# MODE-SELECTOR.net
KiCad netlist of a schematic drawn in Altium Designer
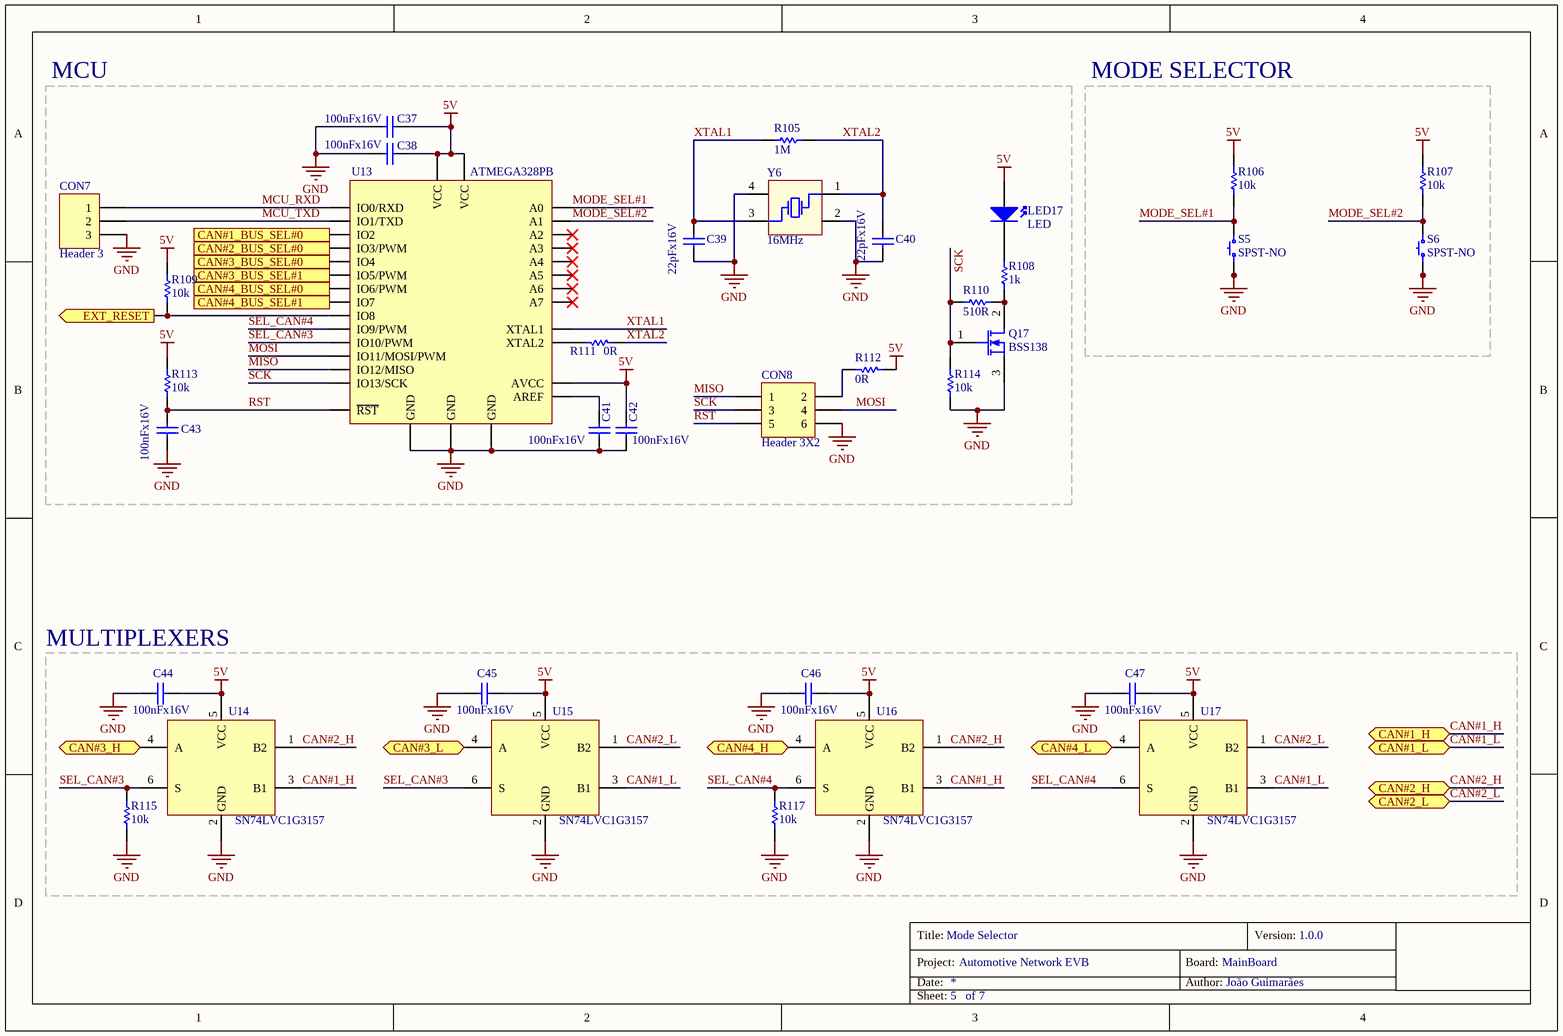
[diagram p0: MODE-SELECTOR.SchDoc]

(export (version "E")
  (design (tool "Eeschema 10.0.6"))
  (components
    (comp (ref "C37")
      (value "100nFx16V")
      (footprint "DISC-0603")
      (description "Capacitor")
      (libsource (lib "IntLib") (part "Cap"))
    )
    (comp (ref "C38")
      (value "100nFx16V")
      (footprint "DISC-0603")
      (description "Capacitor")
      (libsource (lib "IntLib") (part "Cap"))
    )
    (comp (ref "C39")
      (value "22pFx16V")
      (footprint "DISC-0603")
      (description "Capacitor")
      (libsource (lib "IntLib") (part "Cap"))
    )
    (comp (ref "C40")
      (value "22pFx16V")
      (footprint "DISC-0603")
      (description "Capacitor")
      (libsource (lib "IntLib") (part "Cap"))
    )
    (comp (ref "C41")
      (value "100nFx16V")
      (footprint "DISC-0603")
      (description "Capacitor")
      (libsource (lib "IntLib") (part "Cap"))
    )
    (comp (ref "C42")
      (value "100nFx16V")
      (footprint "DISC-0603")
      (description "Capacitor")
      (libsource (lib "IntLib") (part "Cap"))
    )
    (comp (ref "C43")
      (value "100nFx16V")
      (footprint "DISC-0603")
      (description "Capacitor")
      (libsource (lib "IntLib") (part "Cap"))
    )
    (comp (ref "C44")
      (value "100nFx16V")
      (footprint "DISC-0603")
      (description "Capacitor")
      (libsource (lib "IntLib") (part "Cap"))
    )
    (comp (ref "C45")
      (value "100nFx16V")
      (footprint "DISC-0603")
      (description "Capacitor")
      (libsource (lib "IntLib") (part "Cap"))
    )
    (comp (ref "C46")
      (value "100nFx16V")
      (footprint "DISC-0603")
      (description "Capacitor")
      (libsource (lib "IntLib") (part "Cap"))
    )
    (comp (ref "C47")
      (value "100nFx16V")
      (footprint "DISC-0603")
      (description "Capacitor")
      (libsource (lib "IntLib") (part "Cap"))
    )
    (comp (ref "CON7")
      (value "Header 3")
      (footprint "CON-HEADER-1X3-PTH")
      (description "Header, 3-Pin")
      (libsource (lib "IntLib") (part "Header 3"))
    )
    (comp (ref "CON8")
      (value "Header 3X2")
      (footprint "CON-HEADER-2X3-SMD")
      (description "Header, 3-Pin, Dual row")
      (libsource (lib "IntLib") (part "Header 3X2"))
    )
    (comp (ref "LED17") (value "LED") (footprint "DISC-LED-1206") (libsource (lib "IntLib") (part "LED")))
    (comp (ref "Q17")
      (value "BSS138")
      (footprint "DISC-SOT-23")
      (description "Transistor NMOS")
      (libsource (lib "IntLib") (part "Transistor-NMOS(GDS)"))
    )
    (comp (ref "R105")
      (value "1M")
      (footprint "DISC-0603")
      (description "Resistor")
      (libsource (lib "IntLib") (part "Res"))
    )
    (comp (ref "R106")
      (value "10k")
      (footprint "DISC-0603")
      (description "Resistor")
      (libsource (lib "IntLib") (part "Res"))
    )
    (comp (ref "R107")
      (value "10k")
      (footprint "DISC-0603")
      (description "Resistor")
      (libsource (lib "IntLib") (part "Res"))
    )
    (comp (ref "R108") (value "1k") (footprint "DISC-0603") (libsource (lib "IntLib") (part "Res")))
    (comp (ref "R109")
      (value "10k")
      (footprint "DISC-0603")
      (description "Resistor")
      (libsource (lib "IntLib") (part "Res"))
    )
    (comp (ref "R110") (value "510R") (footprint "DISC-0603") (libsource (lib "IntLib") (part "Res")))
    (comp (ref "R111")
      (value "0R")
      (footprint "DISC-0603")
      (description "Resistor")
      (libsource (lib "IntLib") (part "Res"))
    )
    (comp (ref "R112")
      (value "0R")
      (footprint "DISC-0603")
      (description "Resistor")
      (libsource (lib "IntLib") (part "Res"))
    )
    (comp (ref "R113")
      (value "10k")
      (footprint "DISC-0603")
      (description "Resistor")
      (libsource (lib "IntLib") (part "Res"))
    )
    (comp (ref "R114") (value "10k") (footprint "DISC-0603") (libsource (lib "IntLib") (part "Res")))
    (comp (ref "R115")
      (value "10k")
      (footprint "DISC-0603")
      (description "Resistor")
      (libsource (lib "IntLib") (part "Res"))
    )
    (comp (ref "R117")
      (value "10k")
      (footprint "DISC-0603")
      (description "Resistor")
      (libsource (lib "IntLib") (part "Res"))
    )
    (comp (ref "S5")
      (value "SPST-NO")
      (footprint "DISC-PUSHBUTTON-4P-PTH")
      (libsource (lib "IntLib") (part "SPST-NO"))
    )
    (comp (ref "S6")
      (value "SPST-NO")
      (footprint "DISC-PUSHBUTTON-4P-PTH")
      (libsource (lib "IntLib") (part "SPST-NO"))
    )
    (comp (ref "U13")
      (value "ATMEGA328PB")
      (footprint "CI-QFP-32")
      (description "8-bit AVR® RISC-based microcontroller (MCU) with picoPower® technology.")
      (libsource (lib "IntLib") (part "ATMEGA328PB-AU"))
    )
    (comp (ref "U14")
      (value "SN74LVC1G3157")
      (footprint "CI-SOT-23-6")
      (description "Single-Pole Double-Throw Analog Switch")
      (libsource (lib "IntLib") (part "SN74LVC1G3157DBVR"))
    )
    (comp (ref "U15")
      (value "SN74LVC1G3157")
      (footprint "CI-SOT-23-6")
      (description "Single-Pole Double-Throw Analog Switch")
      (libsource (lib "IntLib") (part "SN74LVC1G3157DBVR"))
    )
    (comp (ref "U16")
      (value "SN74LVC1G3157")
      (footprint "CI-SOT-23-6")
      (description "Single-Pole Double-Throw Analog Switch")
      (libsource (lib "IntLib") (part "SN74LVC1G3157DBVR"))
    )
    (comp (ref "U17")
      (value "SN74LVC1G3157")
      (footprint "CI-SOT-23-6")
      (description "Single-Pole Double-Throw Analog Switch")
      (libsource (lib "IntLib") (part "SN74LVC1G3157DBVR"))
    )
    (comp (ref "Y6")
      (value "16MHz")
      (footprint "DISC-CRYSTAL-4P-3.2X2.5")
      (description "XTAL-4-PIN")
      (libsource (lib "IntLib") (part "XTAL-4-PIN"))
    )
  )
  (nets
    (net (code "1") (name "/CAN#1_BUS_SEL#0") (class "Default")
      (node (ref "U13") (pin "32") (pinfunction "IO2_32") (pintype "passive"))
    )
    (net (code "2") (name "/CAN#1_H") (class "Default")
      (node (ref "U14") (pin "3") (pinfunction "B1_3") (pintype "passive"))
      (node (ref "U16") (pin "3") (pinfunction "B1_3") (pintype "passive"))
    )
    (net (code "3") (name "/CAN#1_L") (class "Default")
      (node (ref "U15") (pin "3") (pinfunction "B1_3") (pintype "passive"))
      (node (ref "U17") (pin "3") (pinfunction "B1_3") (pintype "passive"))
    )
    (net (code "4") (name "/CAN#2_BUS_SEL#0") (class "Default")
      (node (ref "U13") (pin "1") (pinfunction "IO3/PWM_1") (pintype "passive"))
    )
    (net (code "5") (name "/CAN#2_H") (class "Default")
      (node (ref "U14") (pin "1") (pinfunction "B2_1") (pintype "passive"))
      (node (ref "U16") (pin "1") (pinfunction "B2_1") (pintype "passive"))
    )
    (net (code "6") (name "/CAN#2_L") (class "Default")
      (node (ref "U15") (pin "1") (pinfunction "B2_1") (pintype "passive"))
      (node (ref "U17") (pin "1") (pinfunction "B2_1") (pintype "passive"))
    )
    (net (code "7") (name "/CAN#3_BUS_SEL#0") (class "Default")
      (node (ref "U13") (pin "2") (pinfunction "IO4_2") (pintype "passive"))
    )
    (net (code "8") (name "/CAN#3_BUS_SEL#1") (class "Default")
      (node (ref "U13") (pin "9") (pinfunction "IO5/PWM_9") (pintype "passive"))
    )
    (net (code "9") (name "/CAN#3_H") (class "Default")
      (node (ref "U14") (pin "4") (pinfunction "A_4") (pintype "passive"))
    )
    (net (code "10") (name "/CAN#3_L") (class "Default")
      (node (ref "U15") (pin "4") (pinfunction "A_4") (pintype "passive"))
    )
    (net (code "11") (name "/CAN#4_BUS_SEL#0") (class "Default")
      (node (ref "U13") (pin "10") (pinfunction "IO6/PWM_10") (pintype "passive"))
    )
    (net (code "12") (name "/CAN#4_BUS_SEL#1") (class "Default")
      (node (ref "U13") (pin "11") (pinfunction "IO7_11") (pintype "passive"))
    )
    (net (code "13") (name "/CAN#4_H") (class "Default")
      (node (ref "U16") (pin "4") (pinfunction "A_4") (pintype "passive"))
    )
    (net (code "14") (name "/CAN#4_L") (class "Default")
      (node (ref "U17") (pin "4") (pinfunction "A_4") (pintype "passive"))
    )
    (net (code "15") (name "/EXT_RESET") (class "Default")
      (node (ref "R109") (pin "2") (pinfunction "2_2") (pintype "passive"))
      (node (ref "U13") (pin "12") (pinfunction "IO8_12") (pintype "passive"))
    )
    (net (code "16") (name "/MCU_RXD") (class "Default")
      (node (ref "CON7") (pin "1") (pinfunction "1_1") (pintype "passive"))
      (node (ref "U13") (pin "30") (pinfunction "IO0/RXD_30") (pintype "passive"))
    )
    (net (code "17") (name "/MCU_TXD") (class "Default")
      (node (ref "CON7") (pin "2") (pinfunction "2_2") (pintype "passive"))
      (node (ref "U13") (pin "31") (pinfunction "IO1/TXD_31") (pintype "passive"))
    )
    (net (code "18") (name "/MISO") (class "Default")
      (node (ref "CON8") (pin "1") (pinfunction "1_1") (pintype "passive"))
      (node (ref "U13") (pin "16") (pinfunction "IO12/MISO_16") (pintype "passive"))
    )
    (net (code "19") (name "/MODE_SEL#1") (class "Default")
      (node (ref "R106") (pin "2") (pinfunction "2_2") (pintype "passive"))
      (node (ref "S5") (pin "3") (pinfunction "3_3") (pintype "passive"))
      (node (ref "S5") (pin "4") (pinfunction "4_4") (pintype "passive"))
      (node (ref "U13") (pin "23") (pinfunction "A0_23") (pintype "passive"))
    )
    (net (code "20") (name "/MODE_SEL#2") (class "Default")
      (node (ref "R107") (pin "2") (pinfunction "2_2") (pintype "passive"))
      (node (ref "S6") (pin "3") (pinfunction "3_3") (pintype "passive"))
      (node (ref "S6") (pin "4") (pinfunction "4_4") (pintype "passive"))
      (node (ref "U13") (pin "24") (pinfunction "A1_24") (pintype "passive"))
    )
    (net (code "21") (name "/MOSI") (class "Default")
      (node (ref "CON8") (pin "4") (pinfunction "4_4") (pintype "passive"))
      (node (ref "U13") (pin "15") (pinfunction "IO11/MOSI/PWM_15") (pintype "passive"))
    )
    (net (code "22") (name "/RST") (class "Default")
      (node (ref "C43") (pin "1") (pinfunction "1_1") (pintype "passive"))
      (node (ref "CON8") (pin "5") (pinfunction "5_5") (pintype "passive"))
      (node (ref "R113") (pin "2") (pinfunction "2_2") (pintype "passive"))
      (node (ref "U13") (pin "29") (pinfunction "~{RST}_29") (pintype "passive"))
    )
    (net (code "23") (name "/SCK") (class "Default")
      (node (ref "CON8") (pin "3") (pinfunction "3_3") (pintype "passive"))
      (node (ref "Q17") (pin "1") (pinfunction "g_1") (pintype "passive"))
      (node (ref "R110") (pin "2") (pinfunction "2_2") (pintype "passive"))
      (node (ref "R114") (pin "2") (pinfunction "2_2") (pintype "passive"))
      (node (ref "U13") (pin "17") (pinfunction "IO13/SCK_17") (pintype "passive"))
    )
    (net (code "24") (name "/SEL_CAN#3") (class "Default")
      (node (ref "R115") (pin "1") (pinfunction "1_1") (pintype "passive"))
      (node (ref "U13") (pin "14") (pinfunction "IO10/PWM_14") (pintype "passive"))
      (node (ref "U14") (pin "6") (pinfunction "S_6") (pintype "passive"))
      (node (ref "U15") (pin "6") (pinfunction "S_6") (pintype "passive"))
    )
    (net (code "25") (name "/SEL_CAN#4") (class "Default")
      (node (ref "R117") (pin "1") (pinfunction "1_1") (pintype "passive"))
      (node (ref "U13") (pin "13") (pinfunction "IO9/PWM_13") (pintype "passive"))
      (node (ref "U16") (pin "6") (pinfunction "S_6") (pintype "passive"))
      (node (ref "U17") (pin "6") (pinfunction "S_6") (pintype "passive"))
    )
    (net (code "26") (name "/XTAL1") (class "Default")
      (node (ref "C39") (pin "2") (pinfunction "2_2") (pintype "passive"))
      (node (ref "R105") (pin "1") (pinfunction "1_1") (pintype "passive"))
      (node (ref "U13") (pin "7") (pinfunction "XTAL1_7") (pintype "passive"))
      (node (ref "Y6") (pin "3") (pinfunction "OSC2_3") (pintype "passive"))
    )
    (net (code "27") (name "/XTAL2") (class "Default")
      (node (ref "C40") (pin "2") (pinfunction "2_2") (pintype "passive"))
      (node (ref "R105") (pin "2") (pinfunction "2_2") (pintype "passive"))
      (node (ref "R111") (pin "1") (pinfunction "1_1") (pintype "passive"))
      (node (ref "Y6") (pin "1") (pinfunction "OSC1_1") (pintype "passive"))
    )
    (net (code "28") (name "5V") (class "Default")
      (node (ref "C37") (pin "2") (pinfunction "2_2") (pintype "passive"))
      (node (ref "C38") (pin "2") (pinfunction "2_2") (pintype "passive"))
      (node (ref "C42") (pin "1") (pinfunction "1_1") (pintype "passive"))
      (node (ref "C44") (pin "2") (pinfunction "2_2") (pintype "passive"))
      (node (ref "C45") (pin "2") (pinfunction "2_2") (pintype "passive"))
      (node (ref "C46") (pin "2") (pinfunction "2_2") (pintype "passive"))
      (node (ref "C47") (pin "2") (pinfunction "2_2") (pintype "passive"))
      (node (ref "LED17") (pin "1") (pinfunction "A_1") (pintype "passive"))
      (node (ref "R106") (pin "1") (pinfunction "1_1") (pintype "passive"))
      (node (ref "R107") (pin "1") (pinfunction "1_1") (pintype "passive"))
      (node (ref "R109") (pin "1") (pinfunction "1_1") (pintype "passive"))
      (node (ref "R112") (pin "2") (pinfunction "2_2") (pintype "passive"))
      (node (ref "R113") (pin "1") (pinfunction "1_1") (pintype "passive"))
      (node (ref "U13") (pin "18") (pinfunction "AVCC_18") (pintype "power_in"))
      (node (ref "U13") (pin "4") (pinfunction "VCC_4") (pintype "power_in"))
      (node (ref "U13") (pin "6") (pinfunction "VCC_6") (pintype "power_in"))
      (node (ref "U14") (pin "5") (pinfunction "VCC_5") (pintype "passive"))
      (node (ref "U15") (pin "5") (pinfunction "VCC_5") (pintype "passive"))
      (node (ref "U16") (pin "5") (pinfunction "VCC_5") (pintype "passive"))
      (node (ref "U17") (pin "5") (pinfunction "VCC_5") (pintype "passive"))
    )
    (net (code "29") (name "GND") (class "Default")
      (node (ref "C37") (pin "1") (pinfunction "1_1") (pintype "passive"))
      (node (ref "C38") (pin "1") (pinfunction "1_1") (pintype "passive"))
      (node (ref "C39") (pin "1") (pinfunction "1_1") (pintype "passive"))
      (node (ref "C40") (pin "1") (pinfunction "1_1") (pintype "passive"))
      (node (ref "C41") (pin "2") (pinfunction "2_2") (pintype "passive"))
      (node (ref "C42") (pin "2") (pinfunction "2_2") (pintype "passive"))
      (node (ref "C43") (pin "2") (pinfunction "2_2") (pintype "passive"))
      (node (ref "C44") (pin "1") (pinfunction "1_1") (pintype "passive"))
      (node (ref "C45") (pin "1") (pinfunction "1_1") (pintype "passive"))
      (node (ref "C46") (pin "1") (pinfunction "1_1") (pintype "passive"))
      (node (ref "C47") (pin "1") (pinfunction "1_1") (pintype "passive"))
      (node (ref "CON7") (pin "3") (pinfunction "3_3") (pintype "passive"))
      (node (ref "CON8") (pin "6") (pinfunction "6_6") (pintype "passive"))
      (node (ref "Q17") (pin "3") (pinfunction "S_3") (pintype "passive"))
      (node (ref "R114") (pin "1") (pinfunction "1_1") (pintype "passive"))
      (node (ref "R115") (pin "2") (pinfunction "2_2") (pintype "passive"))
      (node (ref "R117") (pin "2") (pinfunction "2_2") (pintype "passive"))
      (node (ref "S5") (pin "1") (pinfunction "1_1") (pintype "passive"))
      (node (ref "S5") (pin "2") (pinfunction "2_2") (pintype "passive"))
      (node (ref "S6") (pin "1") (pinfunction "1_1") (pintype "passive"))
      (node (ref "S6") (pin "2") (pinfunction "2_2") (pintype "passive"))
      (node (ref "U13") (pin "21") (pinfunction "GND_21") (pintype "power_in"))
      (node (ref "U13") (pin "3") (pinfunction "GND_3") (pintype "power_in"))
      (node (ref "U13") (pin "5") (pinfunction "GND_5") (pintype "power_in"))
      (node (ref "U14") (pin "2") (pinfunction "GND_2") (pintype "power_in"))
      (node (ref "U15") (pin "2") (pinfunction "GND_2") (pintype "power_in"))
      (node (ref "U16") (pin "2") (pinfunction "GND_2") (pintype "power_in"))
      (node (ref "U17") (pin "2") (pinfunction "GND_2") (pintype "power_in"))
      (node (ref "Y6") (pin "2") (pinfunction "GND_2") (pintype "passive"))
      (node (ref "Y6") (pin "4") (pinfunction "GND_4") (pintype "passive"))
    )
    (net (code "30") (name "Net-(CON8-Pad2)") (class "Default")
      (node (ref "CON8") (pin "2") (pinfunction "2_2") (pintype "passive"))
      (node (ref "R112") (pin "1") (pinfunction "1_1") (pintype "passive"))
    )
    (net (code "31") (name "Net-(LED17-K)") (class "Default")
      (node (ref "LED17") (pin "2") (pinfunction "K_2") (pintype "passive"))
      (node (ref "R108") (pin "2") (pinfunction "2_2") (pintype "passive"))
    )
    (net (code "32") (name "Net-(Q17-D)") (class "Default")
      (node (ref "Q17") (pin "2") (pinfunction "D_2") (pintype "passive"))
      (node (ref "R108") (pin "1") (pinfunction "1_1") (pintype "passive"))
      (node (ref "R110") (pin "1") (pinfunction "1_1") (pintype "passive"))
    )
    (net (code "33") (name "Net-(U13-AREF)") (class "Default")
      (node (ref "C41") (pin "1") (pinfunction "1_1") (pintype "passive"))
      (node (ref "U13") (pin "20") (pinfunction "AREF_20") (pintype "power_in"))
    )
    (net (code "34") (name "Net-(U13-XTAL2)") (class "Default")
      (node (ref "R111") (pin "2") (pinfunction "2_2") (pintype "passive"))
      (node (ref "U13") (pin "8") (pinfunction "XTAL2_8") (pintype "passive"))
    )
    (net (code "35") (name "unconnected-(U13-A2-Pad25)") (class "Default")
      (node (ref "U13") (pin "25") (pinfunction "A2_25") (pintype "passive+no_connect"))
    )
    (net (code "36") (name "unconnected-(U13-A3-Pad26)") (class "Default")
      (node (ref "U13") (pin "26") (pinfunction "A3_26") (pintype "passive+no_connect"))
    )
    (net (code "37") (name "unconnected-(U13-A4-Pad27)") (class "Default")
      (node (ref "U13") (pin "27") (pinfunction "A4_27") (pintype "passive+no_connect"))
    )
    (net (code "38") (name "unconnected-(U13-A5-Pad28)") (class "Default")
      (node (ref "U13") (pin "28") (pinfunction "A5_28") (pintype "passive+no_connect"))
    )
    (net (code "39") (name "unconnected-(U13-A6-Pad19)") (class "Default")
      (node (ref "U13") (pin "19") (pinfunction "A6_19") (pintype "passive+no_connect"))
    )
    (net (code "40") (name "unconnected-(U13-A7-Pad22)") (class "Default")
      (node (ref "U13") (pin "22") (pinfunction "A7_22") (pintype "passive+no_connect"))
    )
  )
)
